# load_cell_amp_JA.net
KiCad netlist of a schematic drawn in EAGLE
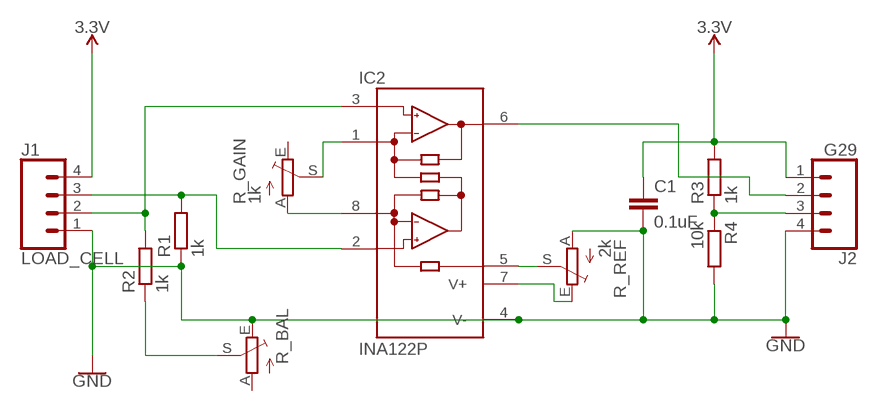
[diagram p0: schematic, sheet 1]

(export (version "E")
  (design (tool "Eeschema 10.0.6"))
  (components
    (comp (ref "C1")
      (value "0.1uF")
      (footprint "eagle-import:C025-024X044")
      (libsource (lib "eagle-import") (part "C-EU025-024X044"))
    )
    (comp (ref "IC2")
      (value "INA122P")
      (footprint "eagle-import:DIL08")
      (fields (field (name "MF") "TEXAS INSTRUMENTS"))
      (libsource (lib "eagle-import") (part "INA122P"))
    )
    (comp (ref "J1")
      (value "LOAD_CELL")
      (footprint "eagle-import:04P")
      (libsource (lib "eagle-import") (part "M04"))
    )
    (comp (ref "J2")
      (value "G29")
      (footprint "eagle-import:04P")
      (libsource (lib "eagle-import") (part "M04"))
    )
    (comp (ref "R1")
      (value "1k")
      (footprint "eagle-import:0207_10")
      (libsource (lib "eagle-import") (part "R-EU_0207/10"))
    )
    (comp (ref "R2")
      (value "1k")
      (footprint "eagle-import:0207_10")
      (libsource (lib "eagle-import") (part "R-EU_0207/10"))
    )
    (comp (ref "R3")
      (value "1k")
      (footprint "eagle-import:0207_10")
      (libsource (lib "eagle-import") (part "R-EU_0207/10"))
    )
    (comp (ref "R4")
      (value "10k")
      (footprint "eagle-import:0207_10")
      (libsource (lib "eagle-import") (part "R-EU_0207/10"))
    )
    (comp (ref "R_BAL")
      (value "10")
      (footprint "eagle-import:RJ9W")
      (libsource (lib "eagle-import") (part "TRIM_EU-RJ9W"))
    )
    (comp (ref "R_GAIN")
      (value "1k")
      (footprint "eagle-import:RJ9W")
      (libsource (lib "eagle-import") (part "TRIM_EU-RJ9W"))
    )
    (comp (ref "R_REF")
      (value "2k")
      (footprint "eagle-import:RJ9W")
      (libsource (lib "eagle-import") (part "TRIM_EU-RJ9W"))
    )
  )
  (nets
    (net (code "1") (name "3.3V") (class "Default")
      (node (ref "C1") (pin "1") (pinfunction "1_1") (pintype "passive"))
      (node (ref "J1") (pin "4") (pinfunction "4_4") (pintype "passive"))
      (node (ref "J2") (pin "1") (pinfunction "1_1") (pintype "passive"))
      (node (ref "R3") (pin "2") (pinfunction "2_2") (pintype "passive"))
    )
    (net (code "2") (name "GND") (class "Default")
      (node (ref "C1") (pin "2") (pinfunction "2_2") (pintype "passive"))
      (node (ref "IC2") (pin "4") (pinfunction "V-_4") (pintype "power_in"))
      (node (ref "J1") (pin "1") (pinfunction "1_1") (pintype "passive"))
      (node (ref "J2") (pin "4") (pinfunction "4_4") (pintype "passive"))
      (node (ref "R1") (pin "1") (pinfunction "1_1") (pintype "passive"))
      (node (ref "R4") (pin "2") (pinfunction "2_2") (pintype "passive"))
      (node (ref "R_BAL") (pin "E") (pinfunction "E_E") (pintype "passive"))
      (node (ref "R_REF") (pin "A") (pinfunction "A_A") (pintype "passive"))
    )
    (net (code "3") (name "Net-(IC2-+IN)") (class "Default")
      (node (ref "IC2") (pin "3") (pinfunction "+IN_3") (pintype "input"))
      (node (ref "J1") (pin "2") (pinfunction "2_2") (pintype "passive"))
      (node (ref "R2") (pin "2") (pinfunction "2_2") (pintype "passive"))
    )
    (net (code "4") (name "Net-(IC2--IN)") (class "Default")
      (node (ref "IC2") (pin "2") (pinfunction "-IN_2") (pintype "input"))
      (node (ref "J1") (pin "3") (pinfunction "3_3") (pintype "passive"))
      (node (ref "R1") (pin "2") (pinfunction "2_2") (pintype "passive"))
    )
    (net (code "5") (name "Net-(IC2-OUT)") (class "Default")
      (node (ref "IC2") (pin "6") (pinfunction "OUT_6") (pintype "output"))
      (node (ref "J2") (pin "2") (pinfunction "2_2") (pintype "passive"))
    )
    (net (code "6") (name "Net-(IC2-REF)") (class "Default")
      (node (ref "IC2") (pin "5") (pinfunction "REF_5") (pintype "passive"))
      (node (ref "R_REF") (pin "S") (pinfunction "S_S") (pintype "passive"))
    )
    (net (code "7") (name "Net-(IC2-RG-Pad1)") (class "Default")
      (node (ref "IC2") (pin "1") (pinfunction "RG_1") (pintype "passive"))
      (node (ref "R_GAIN") (pin "S") (pinfunction "S_S") (pintype "passive"))
    )
    (net (code "8") (name "Net-(IC2-RG-Pad8)") (class "Default")
      (node (ref "IC2") (pin "8") (pinfunction "RG_8") (pintype "passive"))
      (node (ref "R_GAIN") (pin "A") (pinfunction "A_A") (pintype "passive"))
    )
    (net (code "9") (name "Net-(IC2-V+)") (class "Default")
      (node (ref "IC2") (pin "7") (pinfunction "V+_7") (pintype "power_in"))
      (node (ref "R_REF") (pin "E") (pinfunction "E_E") (pintype "passive"))
    )
    (net (code "10") (name "Net-(J2-Pad3)") (class "Default")
      (node (ref "J2") (pin "3") (pinfunction "3_3") (pintype "passive"))
      (node (ref "R3") (pin "1") (pinfunction "1_1") (pintype "passive"))
      (node (ref "R4") (pin "1") (pinfunction "1_1") (pintype "passive"))
    )
    (net (code "11") (name "Net-(R2-Pad1)") (class "Default")
      (node (ref "R2") (pin "1") (pinfunction "1_1") (pintype "passive"))
      (node (ref "R_BAL") (pin "S") (pinfunction "S_S") (pintype "passive"))
    )
    (net (code "12") (name "unconnected-(R_BAL-PadA)") (class "Default")
      (node (ref "R_BAL") (pin "A") (pinfunction "A_A") (pintype "passive"))
    )
    (net (code "13") (name "unconnected-(R_GAIN-PadE)") (class "Default")
      (node (ref "R_GAIN") (pin "E") (pinfunction "E_E") (pintype "passive"))
    )
  )
)
